# Arduino_EvalBoard.net
KiCad netlist of a schematic drawn in Altium Designer
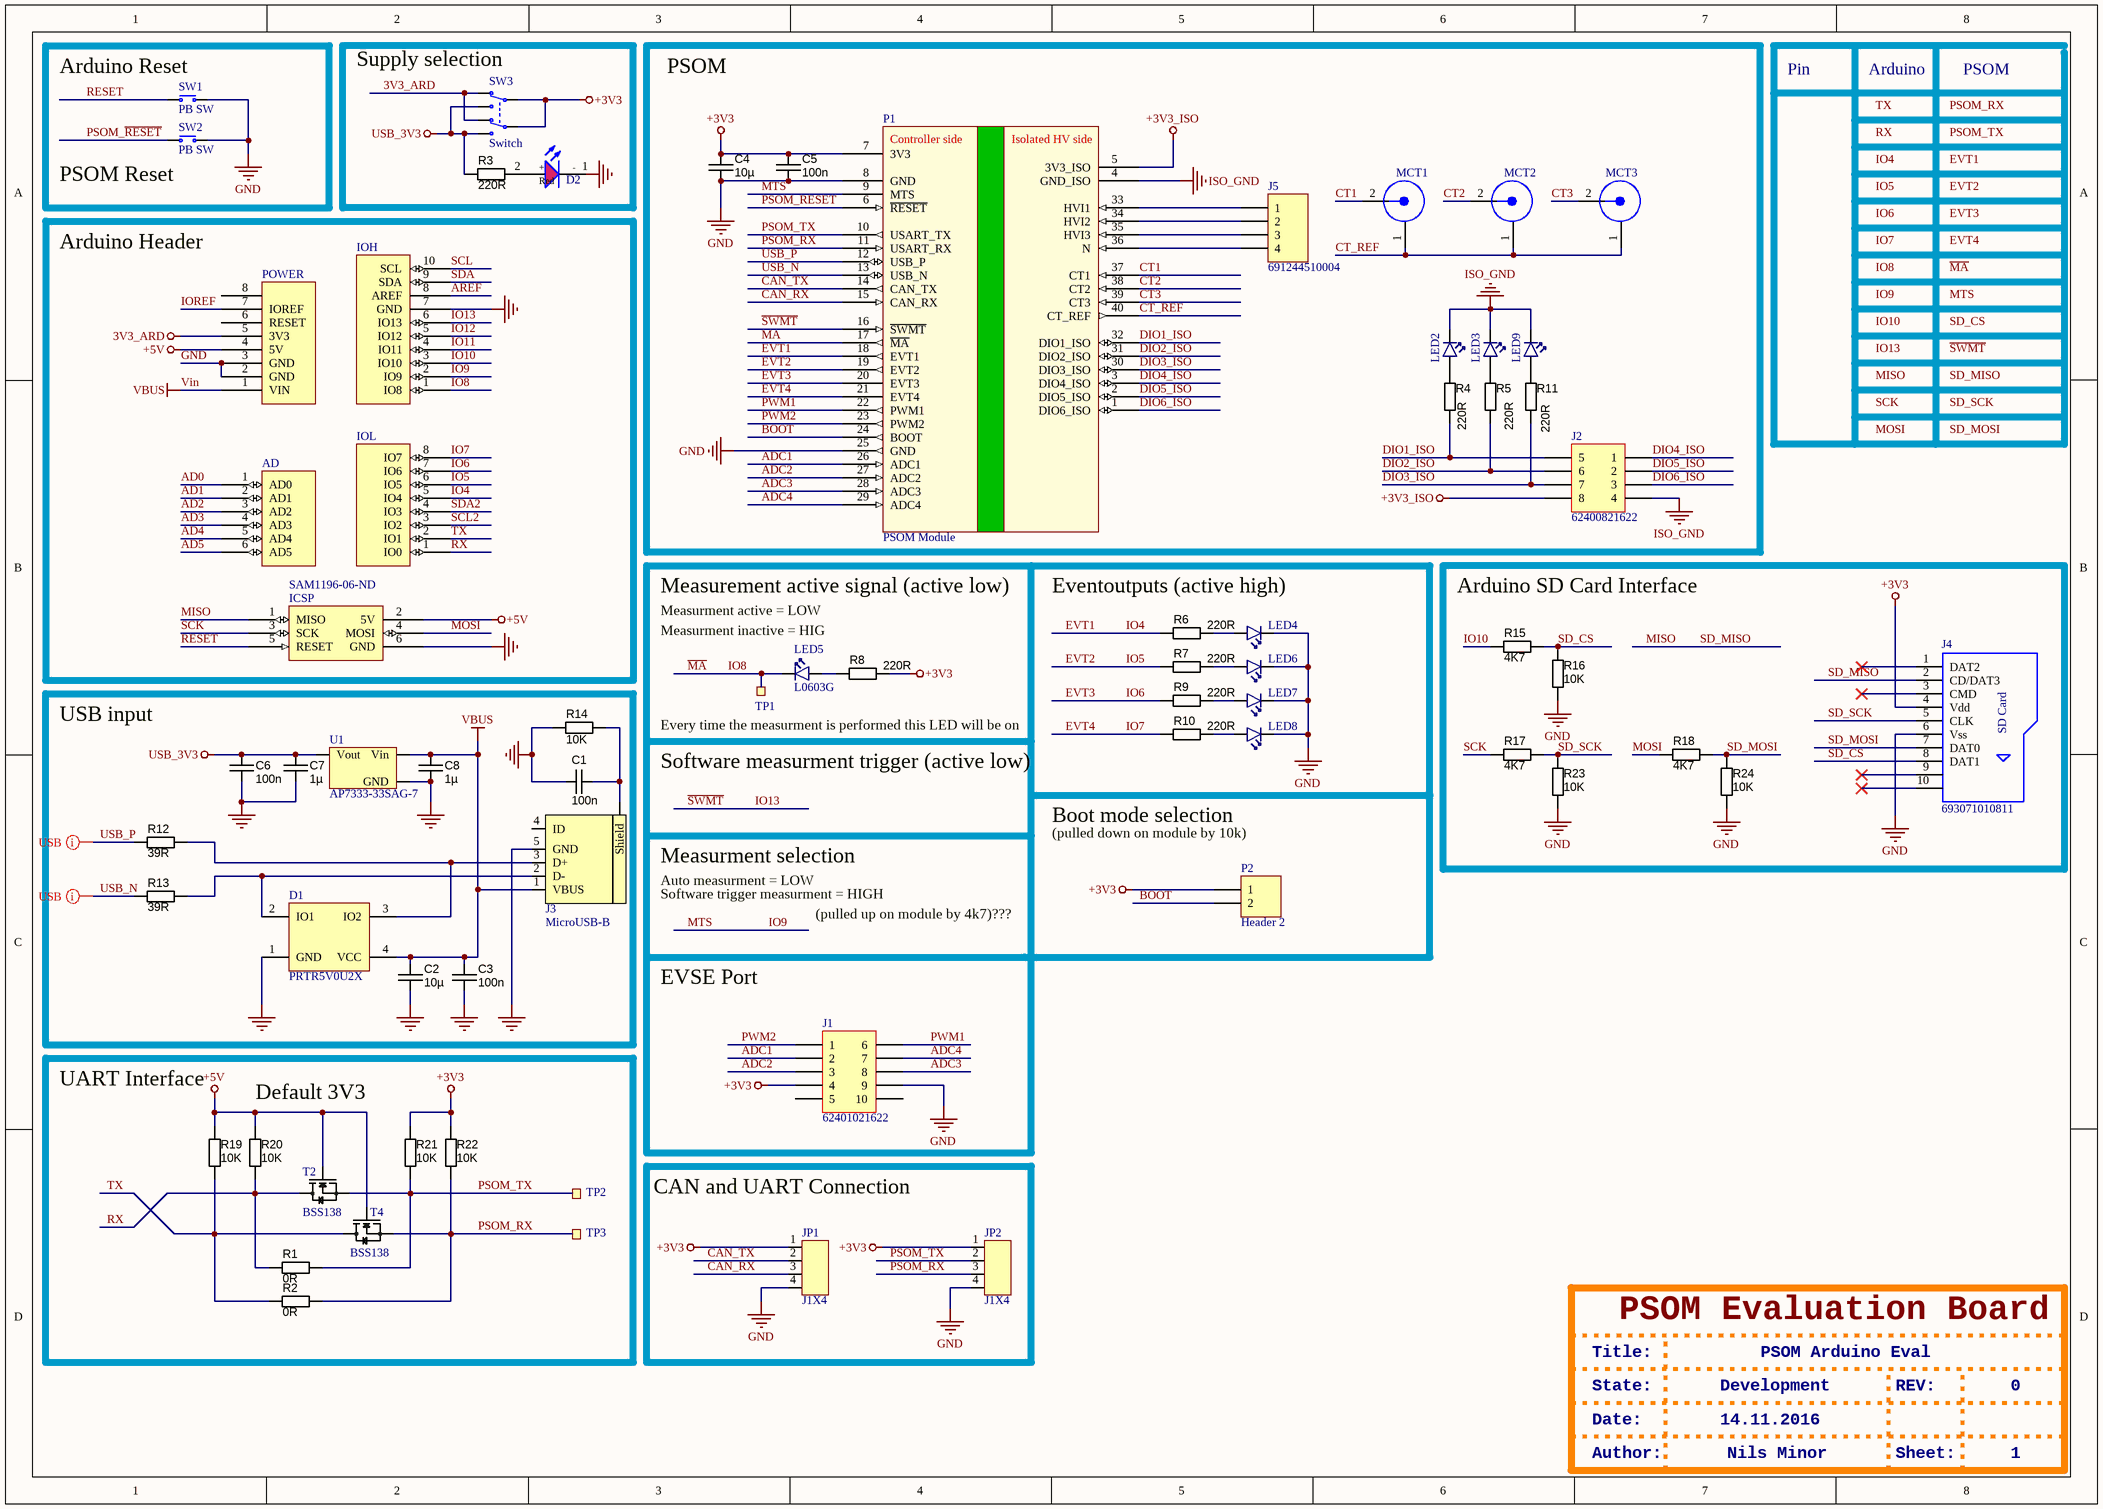
[diagram p0: Arduino EvalBoard.SchDoc]

(export (version "E")
  (design (tool "Eeschema 10.0.6"))
  (components
    (comp (ref "AD")
      (value "AD")
      (footprint "Header:Header 6x1 8.5mm")
      (libsource (lib "Header") (part "AD"))
    )
    (comp (ref "C1")
      (value "100n")
      (footprint "CAPC1608X90N")
      (description "Capacitor SMD Cer 100nF 10% 50V X7R 0603")
      (fields (field (name "TOLERANCE") "±10%") (field (name "Comment") "approved sub OK"))
      (libsource (lib "PBL - Capacitors") (part "CAPC_100n_0603_X7R_50V_10%"))
    )
    (comp (ref "C2")
      (value "10µ")
      (footprint "CAPC2012X135N")
      (description "Capacitor SMD Cer 10uF 10% 10V X5R 0805")
      (fields (field (name "TOLERANCE") "±10%") (field (name "Comment") "approved sub OK"))
      (libsource (lib "PBL - Capacitors") (part "CAPC_10u_0805_10V"))
    )
    (comp (ref "C3")
      (value "100n")
      (footprint "CAPC1608X90N")
      (description "Capacitor SMD Cer 100nF 10% 50V X7R 0603")
      (fields (field (name "TOLERANCE") "±10%") (field (name "Comment") "approved sub OK"))
      (libsource (lib "PBL - Capacitors") (part "CAPC_100n_0603_X7R_50V_10%"))
    )
    (comp (ref "C4")
      (value "10µ")
      (footprint "CAPC2012X135N")
      (description "Capacitor SMD Cer 10uF 10% 10V X5R 0805")
      (fields (field (name "TOLERANCE") "±10%") (field (name "Comment") "approved sub OK"))
      (libsource (lib "PBL - Capacitors") (part "CAPC_10u_0805_10V"))
    )
    (comp (ref "C5")
      (value "100n")
      (footprint "CAPC1608X90N")
      (description "Capacitor SMD Cer 100nF 10% 50V X7R 0603")
      (fields (field (name "TOLERANCE") "±10%") (field (name "Comment") "approved sub OK"))
      (libsource (lib "PBL - Capacitors") (part "CAPC_100n_0603_X7R_50V_10%"))
    )
    (comp (ref "C6")
      (value "100n")
      (footprint "CAPC1608X90N")
      (description "Capacitor SMD Cer 100nF 10% 50V X7R 0603")
      (fields (field (name "TOLERANCE") "±10%") (field (name "Comment") "approved sub OK"))
      (libsource (lib "PBL - Capacitors") (part "CAPC_100n_0603_X7R_50V_10%"))
    )
    (comp (ref "C7")
      (value "1µ")
      (footprint "CAPC1608X90N")
      (description "Capacitor SMD Cer 1uF 10% 16V X7R 0603")
      (fields (field (name "TOLERANCE") "±10%") (field (name "Comment") "approved sub OK"))
      (libsource (lib "PBL - Capacitors") (part "CAPC_1u_0603_X7R_16V_10%"))
    )
    (comp (ref "C8")
      (value "1µ")
      (footprint "CAPC1608X90N")
      (description "Capacitor SMD Cer 1uF 10% 16V X7R 0603")
      (fields (field (name "TOLERANCE") "±10%") (field (name "Comment") "approved sub OK"))
      (libsource (lib "PBL - Capacitors") (part "CAPC_1u_0603_X7R_16V_10%"))
    )
    (comp (ref "D1")
      (value "PRTR5V0U2X")
      (footprint "SOT190P230X110-4L")
      (description "Ultra low capacitance double rail-to-rail ESD protection diode")
      (fields
        (field (name "MANUFACTURER") "NXP")
        (field (name "2ND SOURCE PART NUMBER") "152-4157")
        (field (name "PUBLISHER") "Nordic Semiconductor")
      )
      (libsource (lib "Nordic Discrete DB") (part "PRTR5V0U2X"))
    )
    (comp (ref "D2")
      (value "150060RS75000")
      (footprint "WL-SMCW_0603")
      (description "WL-SMCW SMD chip LED top view mono-color waterclear, 0603, Red")
      (fields (field (name "MANUFACTURER") "Wurth Elektronik") (field (name "CREATED BY") "Baojun Chen"))
      (libsource (lib "WUERTH_SMD_LED") (part "WL-SMCW 0603, 150060RS75000"))
    )
    (comp (ref "ICSP")
      (value "ICSP")
      (footprint "ICSP")
      (fields (field (name "SUPPLIER PART NUMBER 5") "SAM1196-06-ND"))
      (libsource (lib "Header") (part "ICSP"))
    )
    (comp (ref "IOH")
      (value "IOH")
      (footprint "Header:Header 10x1 8.5mm")
      (libsource (lib "Header") (part "IOH"))
    )
    (comp (ref "IOL") (value "IOL") (footprint "Header 8x1 8.5mm") (libsource (lib "Header") (part "IOL")))
    (comp (ref "J1")
      (value "62401021622")
      (footprint "62401021622")
      (description "WR-WTB 2.00mm Male Dual Row Vertical Shrouded Header w. positive locking, 10 pins")
      (fields (field (name "MANUFACTURER") "Wurth Elektronik") (field (name "CREATED BY") "Baojun Chen"))
      (libsource (lib "ALTIUM-WTB_2_00_MALE_HORIZONTAL_SHROUDED_HEADER_6200XX11722-rev16b") (part "62401021622"))
    )
    (comp (ref "J2")
      (value "62400821622")
      (footprint "62400821622")
      (description "WR-WTB 2.00mm Male Dual Row Vertical Shrouded Header w. positive locking, 8 pins")
      (fields (field (name "MANUFACTURER") "Wurth Elektronik") (field (name "CREATED BY") "Baojun Chen"))
      (libsource (lib "ALTIUM-WTB_2_00_MALE_HORIZONTAL_SHROUDED_HEADER_6200XX11722-rev16b") (part "62400821622"))
    )
    (comp (ref "J3")
      (value "MicroUSB-B")
      (footprint "FCI_10118193-0001LF")
      (description "MicroUSB-B-SMT")
      (fields
        (field (name "PART NUMBER") "FCI 10118193-0001LF")
        (field (name "MANUFACTURER") "FCI")
        (field (name "PUBLISHER") "Nordic Semiconductor")
      )
      (libsource (lib "pca10040") (part "MiniUSB-AB-SMT"))
    )
    (comp (ref "J4")
      (value "693071010811")
      (footprint "693071010811")
      (description "WR-CRD Micro SD Card Connector Push & Push - 8 pins")
      (fields (field (name "PUBLISHER") "Wurth Elektronik"))
      (libsource (lib "WUERTH_SD_CARD") (part "693071010811"))
    )
    (comp (ref "J5")
      (value "691244510004")
      (footprint "691244510004")
      (description "WR-TBL Serie 2445 - 5.08mm Horizontal Entry Modular w. Rising Cage Clamp, 04p")
      (fields (field (name "PUBLISHER") "Wurth Elektronik"))
      (libsource (lib "ALTIUM-TBL_5_08_2445_HORIZONTAL_CABLE_ENTRY_W_RISING_CAGE_6912445100xx-rev1") (part "691244510004"))
    )
    (comp (ref "JP1")
      (value "J1X4")
      (footprint "SIP4")
      (description "Jumper 1x4, Stift, gerade, RM 2.54")
      (libsource (lib "WELNER") (part "J1X4"))
    )
    (comp (ref "JP2")
      (value "J1X4")
      (footprint "SIP4")
      (description "Jumper 1x4, Stift, gerade, RM 2.54")
      (libsource (lib "WELNER") (part "J1X4"))
    )
    (comp (ref "LED2")
      (value "L0603G")
      (footprint "LED_0603_G")
      (description "LED 0603, EL19-21SYGC")
      (fields
        (field (name "PART NUMBER") "EL19-21SYGC")
        (field (name "MANUFACTURER") "Everlight")
        (field (name "PUBLISHER") "Nordic Semiconductor")
      )
      (libsource (lib "pca10040") (part "D{colon}LED"))
    )
    (comp (ref "LED3")
      (value "L0603G")
      (footprint "LED_0603_G")
      (description "LED 0603, EL19-21SYGC")
      (fields
        (field (name "PART NUMBER") "EL19-21SYGC")
        (field (name "MANUFACTURER") "Everlight")
        (field (name "PUBLISHER") "Nordic Semiconductor")
      )
      (libsource (lib "pca10040") (part "D{colon}LED"))
    )
    (comp (ref "LED4")
      (value "L0603G")
      (footprint "LED_0603_G")
      (description "LED 0603, EL19-21SYGC")
      (fields
        (field (name "PART NUMBER") "EL19-21SYGC")
        (field (name "MANUFACTURER") "Everlight")
        (field (name "PUBLISHER") "Nordic Semiconductor")
      )
      (libsource (lib "pca10040") (part "D{colon}LED"))
    )
    (comp (ref "LED5")
      (value "L0603G")
      (footprint "LED_0603_G")
      (description "LED 0603, EL19-21SYGC")
      (fields
        (field (name "PART NUMBER") "EL19-21SYGC")
        (field (name "MANUFACTURER") "Everlight")
        (field (name "PUBLISHER") "Nordic Semiconductor")
      )
      (libsource (lib "pca10040") (part "D{colon}LED"))
    )
    (comp (ref "LED6")
      (value "L0603G")
      (footprint "LED_0603_G")
      (description "LED 0603, EL19-21SYGC")
      (fields
        (field (name "PART NUMBER") "EL19-21SYGC")
        (field (name "MANUFACTURER") "Everlight")
        (field (name "PUBLISHER") "Nordic Semiconductor")
      )
      (libsource (lib "pca10040") (part "D{colon}LED"))
    )
    (comp (ref "LED7")
      (value "L0603G")
      (footprint "LED_0603_G")
      (description "LED 0603, EL19-21SYGC")
      (fields
        (field (name "PART NUMBER") "EL19-21SYGC")
        (field (name "MANUFACTURER") "Everlight")
        (field (name "PUBLISHER") "Nordic Semiconductor")
      )
      (libsource (lib "pca10040") (part "D{colon}LED"))
    )
    (comp (ref "LED8")
      (value "L0603G")
      (footprint "LED_0603_G")
      (description "LED 0603, EL19-21SYGC")
      (fields
        (field (name "PART NUMBER") "EL19-21SYGC")
        (field (name "MANUFACTURER") "Everlight")
        (field (name "PUBLISHER") "Nordic Semiconductor")
      )
      (libsource (lib "pca10040") (part "D{colon}LED"))
    )
    (comp (ref "LED9")
      (value "L0603G")
      (footprint "LED_0603_G")
      (description "LED 0603, EL19-21SYGC")
      (fields
        (field (name "PART NUMBER") "EL19-21SYGC")
        (field (name "MANUFACTURER") "Everlight")
        (field (name "PUBLISHER") "Nordic Semiconductor")
      )
      (libsource (lib "pca10040") (part "D{colon}LED"))
    )
    (comp (ref "MCT1")
      (value "~")
      (footprint "BNC_Female")
      (description "BNC Conector")
      (libsource (lib "minor") (part "BNC_Buchse"))
    )
    (comp (ref "MCT2")
      (value "~")
      (footprint "BNC_Female")
      (description "BNC Conector")
      (libsource (lib "minor") (part "BNC_Buchse"))
    )
    (comp (ref "MCT3")
      (value "~")
      (footprint "BNC_Female")
      (description "BNC Conector")
      (libsource (lib "minor") (part "BNC_Buchse"))
    )
    (comp (ref "P1")
      (value "PSOM Module")
      (footprint "PSOM_SMD")
      (description "Power analysis system on a module")
      (fields (field (name "CONTACT") "nilsminor@web.de") (field (name "CREATOR") "Nils Minor"))
      (libsource (lib "PSOM") (part "PSOM_Module_1"))
    )
    (comp (ref "P2")
      (value "Header 2")
      (footprint "HDR1X2")
      (description "Header, 2-Pin")
      (fields (field (name "PUBLISHER") "Altium Limited"))
      (libsource (lib "Miscellaneous Connectors") (part "Header 2"))
    )
    (comp (ref "POWER")
      (value "POWER_UNO")
      (footprint "Header 8x1 8.5mm")
      (libsource (lib "Header") (part "POWER_UNO"))
    )
    (comp (ref "R1")
      (value "0R")
      (footprint "RESC1608N_ZERO")
      (description "Resistor SMD chip 0.0 Ohm 0.1W 0603")
      (fields (field (name "TOLERANCE") "±5%") (field (name "Comment") "Thick Film"))
      (libsource (lib "PBL - Resistors") (part "RES_0R_0603"))
    )
    (comp (ref "R2")
      (value "0R")
      (footprint "RESC1608N_ZERO")
      (description "Resistor SMD chip 0.0 Ohm 0.1W 0603")
      (fields (field (name "TOLERANCE") "±5%") (field (name "Comment") "Thick Film"))
      (libsource (lib "PBL - Resistors") (part "RES_0R_0603"))
    )
    (comp (ref "R3")
      (value "220R")
      (footprint "RESC1608X55N")
      (description "Resistor SMD chip 220 Ohm 0.1W 5% 0603")
      (fields (field (name "TOLERANCE") "±5%") (field (name "Comment") "Thick Film"))
      (libsource (lib "") (part "RES_220R_0603_5%_1"))
    )
    (comp (ref "R4")
      (value "220R")
      (footprint "RESC1005X40N")
      (description "Resistor SMD chip 220 Ohm 0.1W 5% 0603")
      (fields (field (name "TOLERANCE") "±5%") (field (name "Comment") "Thick Film"))
      (libsource (lib "PBL - Resistors") (part "RES_220R_0603_5%"))
    )
    (comp (ref "R5")
      (value "220R")
      (footprint "RESC1005X40N")
      (description "Resistor SMD chip 220 Ohm 0.1W 5% 0603")
      (fields (field (name "TOLERANCE") "±5%") (field (name "Comment") "Thick Film"))
      (libsource (lib "PBL - Resistors") (part "RES_220R_0603_5%"))
    )
    (comp (ref "R6")
      (value "220R")
      (footprint "RESC1005X40N")
      (description "Resistor SMD chip 220 Ohm 0.1W 5% 0603")
      (fields (field (name "TOLERANCE") "±5%") (field (name "Comment") "Thick Film"))
      (libsource (lib "") (part "RES_220R_0603_5%_1"))
    )
    (comp (ref "R7")
      (value "220R")
      (footprint "RESC1005X40N")
      (description "Resistor SMD chip 220 Ohm 0.1W 5% 0603")
      (fields (field (name "TOLERANCE") "±5%") (field (name "Comment") "Thick Film"))
      (libsource (lib "") (part "RES_220R_0603_5%_1"))
    )
    (comp (ref "R8")
      (value "220R")
      (footprint "RESC1005X40N")
      (description "Resistor SMD chip 220 Ohm 0.1W 5% 0603")
      (fields (field (name "TOLERANCE") "±5%") (field (name "Comment") "Thick Film"))
      (libsource (lib "") (part "RES_220R_0603_5%_1"))
    )
    (comp (ref "R9")
      (value "220R")
      (footprint "RESC1005X40N")
      (description "Resistor SMD chip 220 Ohm 0.1W 5% 0603")
      (fields (field (name "TOLERANCE") "±5%") (field (name "Comment") "Thick Film"))
      (libsource (lib "") (part "RES_220R_0603_5%_1"))
    )
    (comp (ref "R10")
      (value "220R")
      (footprint "RESC1005X40N")
      (description "Resistor SMD chip 220 Ohm 0.1W 5% 0603")
      (fields (field (name "TOLERANCE") "±5%") (field (name "Comment") "Thick Film"))
      (libsource (lib "") (part "RES_220R_0603_5%_1"))
    )
    (comp (ref "R11")
      (value "220R")
      (footprint "RESC1005X40N")
      (description "Resistor SMD chip 220 Ohm 0.1W 5% 0603")
      (fields (field (name "TOLERANCE") "±5%") (field (name "Comment") "Thick Film"))
      (libsource (lib "PBL - Resistors") (part "RES_220R_0603_5%"))
    )
    (comp (ref "R12")
      (value "39R")
      (footprint "RESC1608X55N")
      (description "Resistor SMD chip 39 Ohm 0.1W 5% 0603")
      (fields (field (name "TOLERANCE") "±5%") (field (name "Comment") "Thick Film"))
      (libsource (lib "PBL - Resistors") (part "RES_39R_0603_5%"))
    )
    (comp (ref "R13")
      (value "39R")
      (footprint "RESC1608X55N")
      (description "Resistor SMD chip 39 Ohm 0.1W 5% 0603")
      (fields (field (name "TOLERANCE") "±5%") (field (name "Comment") "Thick Film"))
      (libsource (lib "PBL - Resistors") (part "RES_39R_0603_5%"))
    )
    (comp (ref "R14")
      (value "10K")
      (footprint "RESC1005X40N")
      (description "Resistor SMD chip 10k Ohm 0.063W 5% 0402")
      (fields (field (name "TOLERANCE") "±5%") (field (name "Comment") "Thick Film"))
      (libsource (lib "PBL - Resistors") (part "RES_10K_0402_5%"))
    )
    (comp (ref "R15")
      (value "4K7")
      (footprint "RESC1005X40N")
      (description "Resistor SMD chip 4.7K Ohm 0.1W 1% 0603")
      (fields
        (field (name "MANUFACTURER") "Yageo")
        (field (name "MANUFACTURER PART NUMBER") "RC0603FR-074K7L")
      )
      (libsource (lib "PBL - Resistors") (part "RES_4K7_0603_1%"))
    )
    (comp (ref "R16")
      (value "10K")
      (footprint "RESC1005X40N")
      (description "Resistor SMD chip 10k Ohm 0.063W 5% 0402")
      (fields (field (name "TOLERANCE") "±5%") (field (name "Comment") "Thick Film"))
      (libsource (lib "") (part "RES_10K_0402_5%_1"))
    )
    (comp (ref "R17")
      (value "4K7")
      (footprint "RESC1005X40N")
      (description "Resistor SMD chip 4.7K Ohm 0.1W 1% 0603")
      (fields
        (field (name "MANUFACTURER") "Yageo")
        (field (name "MANUFACTURER PART NUMBER") "RC0603FR-074K7L")
      )
      (libsource (lib "PBL - Resistors") (part "RES_4K7_0603_1%"))
    )
    (comp (ref "R18")
      (value "4K7")
      (footprint "RESC1005X40N")
      (description "Resistor SMD chip 4.7K Ohm 0.1W 1% 0603")
      (fields
        (field (name "MANUFACTURER") "Yageo")
        (field (name "MANUFACTURER PART NUMBER") "RC0603FR-074K7L")
      )
      (libsource (lib "PBL - Resistors") (part "RES_4K7_0603_1%"))
    )
    (comp (ref "R19")
      (value "10K")
      (footprint "RESC1005X40N")
      (description "Resistor SMD chip 10k Ohm 0.063W 5% 0402")
      (fields (field (name "TOLERANCE") "±5%") (field (name "Comment") "Thick Film"))
      (libsource (lib "PBL - Resistors") (part "RES_10K_0402_5%"))
    )
    (comp (ref "R20")
      (value "10K")
      (footprint "RESC1005X40N")
      (description "Resistor SMD chip 10k Ohm 0.063W 5% 0402")
      (fields (field (name "TOLERANCE") "±5%") (field (name "Comment") "Thick Film"))
      (libsource (lib "PBL - Resistors") (part "RES_10K_0402_5%"))
    )
    (comp (ref "R21")
      (value "10K")
      (footprint "RESC1005X40N")
      (description "Resistor SMD chip 10k Ohm 0.063W 5% 0402")
      (fields (field (name "TOLERANCE") "±5%") (field (name "Comment") "Thick Film"))
      (libsource (lib "PBL - Resistors") (part "RES_10K_0402_5%"))
    )
    (comp (ref "R22")
      (value "10K")
      (footprint "RESC1005X40N")
      (description "Resistor SMD chip 10k Ohm 0.063W 5% 0402")
      (fields (field (name "TOLERANCE") "±5%") (field (name "Comment") "Thick Film"))
      (libsource (lib "PBL - Resistors") (part "RES_10K_0402_5%"))
    )
    (comp (ref "R23")
      (value "10K")
      (footprint "RESC1005X40N")
      (description "Resistor SMD chip 10k Ohm 0.063W 5% 0402")
      (fields (field (name "TOLERANCE") "±5%") (field (name "Comment") "Thick Film"))
      (libsource (lib "") (part "RES_10K_0402_5%_1"))
    )
    (comp (ref "R24")
      (value "10K")
      (footprint "RESC1005X40N")
      (description "Resistor SMD chip 10k Ohm 0.063W 5% 0402")
      (fields (field (name "TOLERANCE") "±5%") (field (name "Comment") "Thick Film"))
      (libsource (lib "") (part "RES_10K_0402_5%_1"))
    )
    (comp (ref "SW1")
      (value "PB SW")
      (footprint "ALPS_SKHUxxx010_WO_GND")
      (description "ALPS - SKHUALE010 - Tactile Switch, SPNO, SMD, 6.5x6.2x2.5mm")
      (fields
        (field (name "PART NUMBER") "ALPS_SKHUALE010")
        (field (name "MANUFACTURER") "Alps")
        (field (name "PUBLISHER") "Nordic Semiconductor")
      )
      (libsource (lib "pca10040") (part "SW-PB"))
    )
    (comp (ref "SW2")
      (value "PB SW")
      (footprint "ALPS_SKHUxxx010_WO_GND")
      (description "ALPS - SKHUALE010 - Tactile Switch, SPNO, SMD, 6.5x6.2x2.5mm")
      (fields
        (field (name "PART NUMBER") "ALPS_SKHUALE010")
        (field (name "MANUFACTURER") "Alps")
        (field (name "PUBLISHER") "Nordic Semiconductor")
      )
      (libsource (lib "pca10040") (part "SW-PB"))
    )
    (comp (ref "SW3")
      (value "Switch")
      (footprint "JS202011SCQN")
      (description "SMD slide Switch (ON-ON)")
      (fields
        (field (name "PART NUMBER") "JS202011SCQN")
        (field (name "MANUFACTURER") "C&K Components")
        (field (name "PUBLISHER") "Nordic Semiconductor")
      )
      (libsource (lib "pca10040") (part "SW-DPDT"))
    )
    (comp (ref "T2")
      (value "BSS138")
      (footprint "SOT23-3")
      (description "N-Chanel FET,SMD")
      (libsource (lib "BOMEDUS") (part "BSS138"))
    )
    (comp (ref "T4")
      (value "BSS138")
      (footprint "SOT23-3")
      (description "N-Chanel FET,SMD")
      (libsource (lib "BOMEDUS") (part "BSS138"))
    )
    (comp (ref "TP1")
      (value "Ø1.0mm,SMD")
      (footprint "TP_SMD_Ø1.0mm")
      (description "1.0mm circular SMD testpad")
      (fields
        (field (name "PART NUMBER") "TP_SMD_Ø1.0MM")
        (field (name "MANUFACTURER") "Nordic Semiconductor")
        (field (name "PUBLISHER") "Nordic Semiconductor")
      )
      (libsource (lib "pca10040") (part "TESTPAD"))
    )
    (comp (ref "TP2")
      (value "Ø1.0mm,SMD")
      (footprint "TP_SMD_Ø1.0mm")
      (description "1.0mm circular SMD testpad")
      (fields
        (field (name "PART NUMBER") "TP_SMD_Ø1.0MM")
        (field (name "MANUFACTURER") "Nordic Semiconductor")
        (field (name "PUBLISHER") "Nordic Semiconductor")
      )
      (libsource (lib "") (part "TESTPAD_1"))
    )
    (comp (ref "TP3")
      (value "Ø1.0mm,SMD")
      (footprint "TP_SMD_Ø1.0mm")
      (description "1.0mm circular SMD testpad")
      (fields
        (field (name "PART NUMBER") "TP_SMD_Ø1.0MM")
        (field (name "MANUFACTURER") "Nordic Semiconductor")
        (field (name "PUBLISHER") "Nordic Semiconductor")
      )
      (libsource (lib "") (part "TESTPAD_1"))
    )
    (comp (ref "U1")
      (value "AP7333-33SAG-7")
      (footprint "SOT-23A")
      (description "300mA, Low Quiescent Current, Fast Transient Low Dropout Linear Regulator")
      (fields (field (name "MANUFACTURER") "Diodes Incorporated"))
      (libsource (lib "pca10040") (part "AP7333-XXSAG"))
    )
  )
  (nets
    (net (code "1") (name "+3V3") (class "Default")
      (node (ref "C4") (pin "1") (pintype "passive"))
      (node (ref "C5") (pin "1") (pintype "passive"))
      (node (ref "J1") (pin "4") (pinfunction "4_4") (pintype "passive"))
      (node (ref "J4") (pin "4") (pinfunction "Vdd_4") (pintype "passive"))
      (node (ref "JP1") (pin "1") (pintype "passive"))
      (node (ref "JP2") (pin "1") (pintype "passive"))
      (node (ref "P1") (pin "7") (pinfunction "3V3_7") (pintype "power_in"))
      (node (ref "P2") (pin "1") (pinfunction "1_1") (pintype "passive"))
      (node (ref "R21") (pin "2") (pinfunction "2_2") (pintype "passive"))
      (node (ref "R22") (pin "2") (pinfunction "2_2") (pintype "passive"))
      (node (ref "R8") (pin "1") (pinfunction "1_1") (pintype "passive"))
      (node (ref "SW3") (pin "2") (pinfunction "COM-1_2") (pintype "passive"))
      (node (ref "SW3") (pin "5") (pinfunction "COM-2_5") (pintype "passive"))
    )
    (net (code "2") (name "+3V3_ISO") (class "Default")
      (node (ref "J2") (pin "8") (pinfunction "8_8") (pintype "passive"))
      (node (ref "P1") (pin "5") (pinfunction "3V3_ISO_5") (pintype "power_in"))
    )
    (net (code "3") (name "+5V") (class "Default")
      (node (ref "ICSP") (pin "2") (pinfunction "5V_2") (pintype "power_in"))
      (node (ref "POWER") (pin "4") (pinfunction "5V_4") (pintype "power_in"))
      (node (ref "R19") (pin "2") (pinfunction "2_2") (pintype "passive"))
      (node (ref "R20") (pin "2") (pinfunction "2_2") (pintype "passive"))
      (node (ref "T2") (pin "1") (pinfunction "G_1") (pintype "passive"))
      (node (ref "T4") (pin "1") (pinfunction "G_1") (pintype "passive"))
    )
    (net (code "5") (name "/AD0") (class "Default")
      (node (ref "AD") (pin "1") (pinfunction "AD0_1") (pintype "bidirectional"))
    )
    (net (code "6") (name "/AD1") (class "Default")
      (node (ref "AD") (pin "2") (pinfunction "AD1_2") (pintype "bidirectional"))
    )
    (net (code "7") (name "/AD2") (class "Default")
      (node (ref "AD") (pin "3") (pinfunction "AD2_3") (pintype "bidirectional"))
    )
    (net (code "8") (name "/AD3") (class "Default")
      (node (ref "AD") (pin "4") (pinfunction "AD3_4") (pintype "bidirectional"))
    )
    (net (code "9") (name "/AD4") (class "Default")
      (node (ref "AD") (pin "5") (pinfunction "AD4_5") (pintype "bidirectional"))
    )
    (net (code "10") (name "/AD5") (class "Default")
      (node (ref "AD") (pin "6") (pinfunction "AD5_6") (pintype "bidirectional"))
    )
    (net (code "11") (name "/ADC1") (class "Default")
      (node (ref "J1") (pin "2") (pinfunction "2_2") (pintype "passive"))
      (node (ref "P1") (pin "26") (pinfunction "ADC1_26") (pintype "input"))
    )
    (net (code "12") (name "/ADC2") (class "Default")
      (node (ref "J1") (pin "3") (pinfunction "3_3") (pintype "passive"))
      (node (ref "P1") (pin "27") (pinfunction "ADC2_27") (pintype "input"))
    )
    (net (code "13") (name "/ADC3") (class "Default")
      (node (ref "J1") (pin "8") (pinfunction "8_8") (pintype "passive"))
      (node (ref "P1") (pin "28") (pinfunction "ADC3_28") (pintype "input"))
    )
    (net (code "14") (name "/ADC4") (class "Default")
      (node (ref "J1") (pin "7") (pinfunction "7_7") (pintype "passive"))
      (node (ref "P1") (pin "29") (pinfunction "ADC4_29") (pintype "input"))
    )
    (net (code "15") (name "/AREF") (class "Default")
      (node (ref "IOH") (pin "8") (pinfunction "AREF_8") (pintype "passive"))
    )
    (net (code "16") (name "/BOOT") (class "Default")
      (node (ref "P1") (pin "24") (pinfunction "BOOT_24") (pintype "output"))
      (node (ref "P2") (pin "2") (pinfunction "2_2") (pintype "passive"))
    )
    (net (code "17") (name "/CAN_RX") (class "Default")
      (node (ref "JP1") (pin "3") (pintype "passive"))
      (node (ref "P1") (pin "15") (pinfunction "CAN_RX_15") (pintype "input"))
    )
    (net (code "18") (name "/CAN_TX") (class "Default")
      (node (ref "JP1") (pin "2") (pintype "passive"))
      (node (ref "P1") (pin "14") (pinfunction "CAN_TX_14") (pintype "output"))
    )
    (net (code "19") (name "/CT1") (class "Default")
      (node (ref "MCT1") (pin "2") (pinfunction "2_2") (pintype "passive"))
      (node (ref "P1") (pin "37") (pinfunction "CT1_37") (pintype "input"))
    )
    (net (code "20") (name "/CT2") (class "Default")
      (node (ref "MCT2") (pin "2") (pinfunction "2_2") (pintype "passive"))
      (node (ref "P1") (pin "38") (pinfunction "CT2_38") (pintype "input"))
    )
    (net (code "21") (name "/CT3") (class "Default")
      (node (ref "MCT3") (pin "2") (pinfunction "2_2") (pintype "passive"))
      (node (ref "P1") (pin "39") (pinfunction "CT3_39") (pintype "input"))
    )
    (net (code "22") (name "/CT_REF") (class "Default")
      (node (ref "MCT1") (pin "1") (pinfunction "1_1") (pintype "passive"))
      (node (ref "MCT2") (pin "1") (pinfunction "1_1") (pintype "passive"))
      (node (ref "MCT3") (pin "1") (pinfunction "1_1") (pintype "passive"))
      (node (ref "P1") (pin "40") (pinfunction "CT_REF_40") (pintype "output"))
    )
    (net (code "23") (name "/DIO1_ISO") (class "Default")
      (node (ref "J2") (pin "5") (pinfunction "5_5") (pintype "passive"))
      (node (ref "P1") (pin "32") (pinfunction "DIO1_ISO_32") (pintype "bidirectional"))
      (node (ref "R4") (pin "2") (pinfunction "2_2") (pintype "passive"))
    )
    (net (code "24") (name "/DIO2_ISO") (class "Default")
      (node (ref "J2") (pin "6") (pinfunction "6_6") (pintype "passive"))
      (node (ref "P1") (pin "31") (pinfunction "DIO2_ISO_31") (pintype "bidirectional"))
      (node (ref "R5") (pin "2") (pinfunction "2_2") (pintype "passive"))
    )
    (net (code "25") (name "/DIO3_ISO") (class "Default")
      (node (ref "J2") (pin "7") (pinfunction "7_7") (pintype "passive"))
      (node (ref "P1") (pin "30") (pinfunction "DIO3_ISO_30") (pintype "bidirectional"))
      (node (ref "R11") (pin "2") (pinfunction "2_2") (pintype "passive"))
    )
    (net (code "26") (name "/DIO4_ISO") (class "Default")
      (node (ref "J2") (pin "1") (pinfunction "1_1") (pintype "passive"))
      (node (ref "P1") (pin "3") (pinfunction "DIO4_ISO_3") (pintype "bidirectional"))
    )
    (net (code "27") (name "/DIO5_ISO") (class "Default")
      (node (ref "J2") (pin "2") (pinfunction "2_2") (pintype "passive"))
      (node (ref "P1") (pin "2") (pinfunction "DIO5_ISO_2") (pintype "bidirectional"))
    )
    (net (code "28") (name "/DIO6_ISO") (class "Default")
      (node (ref "J2") (pin "3") (pinfunction "3_3") (pintype "passive"))
      (node (ref "P1") (pin "1") (pinfunction "DIO6_ISO_1") (pintype "bidirectional"))
    )
    (net (code "29") (name "/EVT1") (class "Default")
      (node (ref "IOL") (pin "5") (pinfunction "IO4_5") (pintype "bidirectional"))
      (node (ref "P1") (pin "18") (pinfunction "EVT1_18") (pintype "output"))
      (node (ref "R6") (pin "2") (pinfunction "2_2") (pintype "passive"))
    )
    (net (code "30") (name "/EVT2") (class "Default")
      (node (ref "IOL") (pin "6") (pinfunction "IO5_6") (pintype "bidirectional"))
      (node (ref "P1") (pin "19") (pinfunction "EVT2_19") (pintype "output"))
      (node (ref "R7") (pin "2") (pinfunction "2_2") (pintype "passive"))
    )
    (net (code "31") (name "/EVT3") (class "Default")
      (node (ref "IOL") (pin "7") (pinfunction "IO6_7") (pintype "bidirectional"))
      (node (ref "P1") (pin "20") (pinfunction "EVT3_20") (pintype "passive"))
      (node (ref "R9") (pin "2") (pinfunction "2_2") (pintype "passive"))
    )
    (net (code "32") (name "/EVT4") (class "Default")
      (node (ref "IOL") (pin "8") (pinfunction "IO7_8") (pintype "bidirectional"))
      (node (ref "P1") (pin "21") (pinfunction "EVT4_21") (pintype "passive"))
      (node (ref "R10") (pin "2") (pinfunction "2_2") (pintype "passive"))
    )
    (net (code "33") (name "/IO8") (class "Default")
      (node (ref "IOH") (pin "1") (pinfunction "IO8_1") (pintype "bidirectional"))
      (node (ref "LED5") (pin "1") (pinfunction "C_1") (pintype "passive"))
      (node (ref "P1") (pin "17") (pinfunction "~{MA}_17") (pintype "output"))
      (node (ref "TP1") (pin "1") (pinfunction "1_1") (pintype "passive"))
    )
    (net (code "34") (name "/IO9") (class "Default")
      (node (ref "IOH") (pin "2") (pinfunction "IO9_2") (pintype "bidirectional"))
      (node (ref "P1") (pin "9") (pinfunction "MTS_9") (pintype "passive"))
    )
    (net (code "35") (name "/IO10") (class "Default")
      (node (ref "IOH") (pin "3") (pinfunction "IO10_3") (pintype "bidirectional"))
      (node (ref "R15") (pin "2") (pinfunction "2_2") (pintype "passive"))
    )
    (net (code "36") (name "/IO11") (class "Default")
      (node (ref "IOH") (pin "4") (pinfunction "IO11_4") (pintype "bidirectional"))
    )
    (net (code "37") (name "/IO12") (class "Default")
      (node (ref "IOH") (pin "5") (pinfunction "IO12_5") (pintype "bidirectional"))
    )
    (net (code "38") (name "/IO13") (class "Default")
      (node (ref "IOH") (pin "6") (pinfunction "IO13_6") (pintype "bidirectional"))
      (node (ref "P1") (pin "16") (pinfunction "~{SWMT}_16") (pintype "input"))
    )
    (net (code "39") (name "/IOREF") (class "Default")
      (node (ref "POWER") (pin "7") (pinfunction "IOREF_7") (pintype "power_in"))
    )
    (net (code "40") (name "/MISO") (class "Default")
      (node (ref "ICSP") (pin "1") (pinfunction "MISO_1") (pintype "bidirectional"))
      (node (ref "J4") (pin "2") (pinfunction "CD/DAT3_2") (pintype "passive"))
    )
    (net (code "41") (name "/MOSI") (class "Default")
      (node (ref "ICSP") (pin "4") (pinfunction "MOSI_4") (pintype "bidirectional"))
      (node (ref "R18") (pin "2") (pinfunction "2_2") (pintype "passive"))
    )
    (net (code "42") (name "/PSOM_RX") (class "Default")
      (node (ref "JP2") (pin "3") (pintype "passive"))
      (node (ref "P1") (pin "11") (pinfunction "USART_RX_11") (pintype "input"))
      (node (ref "R2") (pin "2") (pinfunction "2_2") (pintype "passive"))
      (node (ref "R22") (pin "1") (pinfunction "1_1") (pintype "passive"))
      (node (ref "T4") (pin "2") (pinfunction "S_2") (pintype "passive"))
      (node (ref "TP3") (pin "1") (pinfunction "1_1") (pintype "passive"))
    )
    (net (code "43") (name "/PSOM_TX") (class "Default")
      (node (ref "JP2") (pin "2") (pintype "passive"))
      (node (ref "P1") (pin "10") (pinfunction "USART_TX_10") (pintype "output"))
      (node (ref "R1") (pin "2") (pinfunction "2_2") (pintype "passive"))
      (node (ref "R21") (pin "1") (pinfunction "1_1") (pintype "passive"))
      (node (ref "T2") (pin "2") (pinfunction "S_2") (pintype "passive"))
      (node (ref "TP2") (pin "1") (pinfunction "1_1") (pintype "passive"))
    )
    (net (code "44") (name "/PSOM_~{RESET}") (class "Default")
      (node (ref "P1") (pin "6") (pinfunction "~{RESET}_6") (pintype "input"))
      (node (ref "SW2") (pin "2") (pinfunction "COM_2") (pintype "passive"))
    )
    (net (code "45") (name "/PWM1") (class "Default")
      (node (ref "J1") (pin "6") (pinfunction "6_6") (pintype "passive"))
      (node (ref "P1") (pin "22") (pinfunction "PWM1_22") (pintype "output"))
    )
    (net (code "46") (name "/PWM2") (class "Default")
      (node (ref "J1") (pin "1") (pinfunction "1_1") (pintype "passive"))
      (node (ref "P1") (pin "23") (pinfunction "PWM2_23") (pintype "output"))
    )
    (net (code "47") (name "/RESET") (class "Default")
      (node (ref "ICSP") (pin "5") (pinfunction "RESET_5") (pintype "input"))
      (node (ref "SW1") (pin "2") (pinfunction "COM_2") (pintype "passive"))
    )
    (net (code "48") (name "/RX") (class "Default")
      (node (ref "IOL") (pin "1") (pinfunction "IO0_1") (pintype "bidirectional"))
      (node (ref "R1") (pin "1") (pinfunction "1_1") (pintype "passive"))
      (node (ref "R20") (pin "1") (pinfunction "1_1") (pintype "passive"))
      (node (ref "T2") (pin "3") (pinfunction "D_3") (pintype "passive"))
    )
    (net (code "49") (name "/SCK") (class "Default")
      (node (ref "ICSP") (pin "3") (pinfunction "SCK_3") (pintype "bidirectional"))
      (node (ref "R17") (pin "2") (pinfunction "2_2") (pintype "passive"))
    )
    (net (code "50") (name "/SCL") (class "Default")
      (node (ref "IOH") (pin "10") (pinfunction "SCL_10") (pintype "bidirectional"))
    )
    (net (code "51") (name "/SCL2") (class "Default")
      (node (ref "IOL") (pin "3") (pinfunction "IO2_3") (pintype "bidirectional"))
    )
    (net (code "52") (name "/SDA") (class "Default")
      (node (ref "IOH") (pin "9") (pinfunction "SDA_9") (pintype "bidirectional"))
    )
    (net (code "53") (name "/SDA2") (class "Default")
      (node (ref "IOL") (pin "4") (pinfunction "IO3_4") (pintype "bidirectional"))
    )
    (net (code "54") (name "/SD_CS") (class "Default")
      (node (ref "J4") (pin "8") (pinfunction "DAT1_8") (pintype "passive"))
      (node (ref "R15") (pin "1") (pinfunction "1_1") (pintype "passive"))
      (node (ref "R16") (pin "1") (pinfunction "1_1") (pintype "passive"))
    )
    (net (code "55") (name "/SD_MOSI") (class "Default")
      (node (ref "J4") (pin "7") (pinfunction "DAT0_7") (pintype "passive"))
      (node (ref "R18") (pin "1") (pinfunction "1_1") (pintype "passive"))
      (node (ref "R24") (pin "1") (pinfunction "1_1") (pintype "passive"))
    )
    (net (code "56") (name "/SD_SCK") (class "Default")
      (node (ref "J4") (pin "5") (pinfunction "CLK_5") (pintype "passive"))
      (node (ref "R17") (pin "1") (pinfunction "1_1") (pintype "passive"))
      (node (ref "R23") (pin "1") (pinfunction "1_1") (pintype "passive"))
    )
    (net (code "57") (name "/TX") (class "Default")
      (node (ref "IOL") (pin "2") (pinfunction "IO1_2") (pintype "bidirectional"))
      (node (ref "R19") (pin "1") (pinfunction "1_1") (pintype "passive"))
      (node (ref "R2") (pin "1") (pinfunction "1_1") (pintype "passive"))
      (node (ref "T4") (pin "3") (pinfunction "D_3") (pintype "passive"))
    )
    (net (code "58") (name "/USB_N") (class "Default")
      (node (ref "P1") (pin "13") (pinfunction "USB_N_13") (pintype "bidirectional"))
      (node (ref "R13") (pin "1") (pinfunction "1_1") (pintype "passive"))
    )
    (net (code "59") (name "/USB_P") (class "Default")
      (node (ref "P1") (pin "12") (pinfunction "USB_P_12") (pintype "bidirectional"))
      (node (ref "R12") (pin "1") (pinfunction "1_1") (pintype "passive"))
    )
    (net (code "60") (name "3V3_ARD") (class "Default")
      (node (ref "POWER") (pin "5") (pinfunction "3V3_5") (pintype "power_in"))
      (node (ref "SW3") (pin "3") (pinfunction "N.C-1_3") (pintype "passive"))
      (node (ref "SW3") (pin "6") (pinfunction "N.C-2_6") (pintype "passive"))
    )
    (net (code "61") (name "GND") (class "Default")
      (node (ref "C1") (pin "1") (pintype "passive"))
      (node (ref "C2") (pin "2") (pintype "passive"))
      (node (ref "C3") (pin "2") (pintype "passive"))
      (node (ref "C4") (pin "2") (pintype "passive"))
      (node (ref "C5") (pin "2") (pintype "passive"))
      (node (ref "C6") (pin "1") (pintype "passive"))
      (node (ref "C7") (pin "2") (pintype "passive"))
      (node (ref "C8") (pin "2") (pintype "passive"))
      (node (ref "D1") (pin "1") (pinfunction "GND_1") (pintype "passive"))
      (node (ref "D2") (pin "1") (pinfunction "-_1") (pintype "passive"))
      (node (ref "ICSP") (pin "6") (pinfunction "GND_6") (pintype "power_in"))
      (node (ref "IOH") (pin "7") (pinfunction "GND_7") (pintype "power_in"))
      (node (ref "J1") (pin "9") (pinfunction "9_9") (pintype "passive"))
      (node (ref "J3") (pin "5") (pinfunction "GND_5") (pintype "power_in"))
      (node (ref "J4") (pin "6") (pinfunction "Vss_6") (pintype "passive"))
      (node (ref "JP1") (pin "4") (pintype "passive"))
      (node (ref "JP2") (pin "4") (pintype "passive"))
      (node (ref "LED4") (pin "1") (pinfunction "C_1") (pintype "passive"))
      (node (ref "LED6") (pin "1") (pinfunction "C_1") (pintype "passive"))
      (node (ref "LED7") (pin "1") (pinfunction "C_1") (pintype "passive"))
      (node (ref "LED8") (pin "1") (pinfunction "C_1") (pintype "passive"))
      (node (ref "P1") (pin "25") (pinfunction "GND_25") (pintype "output"))
      (node (ref "P1") (pin "8") (pinfunction "GND_8") (pintype "power_in"))
      (node (ref "POWER") (pin "2") (pinfunction "GND_2") (pintype "power_in"))
      (node (ref "POWER") (pin "3") (pinfunction "GND_3") (pintype "power_in"))
      (node (ref "R14") (pin "1") (pinfunction "1_1") (pintype "passive"))
      (node (ref "R16") (pin "2") (pinfunction "2_2") (pintype "passive"))
      (node (ref "R23") (pin "2") (pinfunction "2_2") (pintype "passive"))
      (node (ref "R24") (pin "2") (pinfunction "2_2") (pintype "passive"))
      (node (ref "SW1") (pin "1") (pinfunction "N.O_1") (pintype "passive"))
      (node (ref "SW2") (pin "1") (pinfunction "N.O_1") (pintype "passive"))
      (node (ref "U1") (pin "3") (pinfunction "GND_3") (pintype "passive"))
    )
    (net (code "62") (name "ISO_GND") (class "Default")
      (node (ref "J2") (pin "4") (pinfunction "4_4") (pintype "passive"))
      (node (ref "LED2") (pin "1") (pinfunction "C_1") (pintype "passive"))
      (node (ref "LED3") (pin "1") (pinfunction "C_1") (pintype "passive"))
      (node (ref "LED9") (pin "1") (pinfunction "C_1") (pintype "passive"))
      (node (ref "P1") (pin "4") (pinfunction "GND_ISO_4") (pintype "power_in"))
    )
    (net (code "63") (name "Net-(D1-IO1)") (class "Default")
      (node (ref "D1") (pin "2") (pinfunction "IO1_2") (pintype "passive"))
      (node (ref "J3") (pin "2") (pinfunction "D-_2") (pintype "passive"))
      (node (ref "R13") (pin "2") (pinfunction "2_2") (pintype "passive"))
    )
    (net (code "64") (name "Net-(D1-IO2)") (class "Default")
      (node (ref "D1") (pin "3") (pinfunction "IO2_3") (pintype "passive"))
      (node (ref "J3") (pin "3") (pinfunction "D+_3") (pintype "passive"))
      (node (ref "R12") (pin "2") (pinfunction "2_2") (pintype "passive"))
    )
    (net (code "65") (name "Net-(D2-+)") (class "Default")
      (node (ref "D2") (pin "2") (pinfunction "+_2") (pintype "passive"))
      (node (ref "R3") (pin "1") (pinfunction "1_1") (pintype "passive"))
    )
    (net (code "66") (name "Net-(J3-Shield)") (class "Default")
      (node (ref "C1") (pin "2") (pintype "passive"))
      (node (ref "J3") (pin "6") (pinfunction "Shield_6") (pintype "power_in"))
      (node (ref "R14") (pin "2") (pinfunction "2_2") (pintype "passive"))
    )
    (net (code "67") (name "Net-(LED2-A)") (class "Default")
      (node (ref "LED2") (pin "2") (pinfunction "A_2") (pintype "passive"))
      (node (ref "R4") (pin "1") (pinfunction "1_1") (pintype "passive"))
    )
    (net (code "68") (name "Net-(LED3-A)") (class "Default")
      (node (ref "LED3") (pin "2") (pinfunction "A_2") (pintype "passive"))
      (node (ref "R5") (pin "1") (pinfunction "1_1") (pintype "passive"))
    )
    (net (code "69") (name "Net-(LED4-A)") (class "Default")
      (node (ref "LED4") (pin "2") (pinfunction "A_2") (pintype "passive"))
      (node (ref "R6") (pin "1") (pinfunction "1_1") (pintype "passive"))
    )
    (net (code "70") (name "Net-(LED5-A)") (class "Default")
      (node (ref "LED5") (pin "2") (pinfunction "A_2") (pintype "passive"))
      (node (ref "R8") (pin "2") (pinfunction "2_2") (pintype "passive"))
    )
    (net (code "71") (name "Net-(LED6-A)") (class "Default")
      (node (ref "LED6") (pin "2") (pinfunction "A_2") (pintype "passive"))
      (node (ref "R7") (pin "1") (pinfunction "1_1") (pintype "passive"))
    )
    (net (code "72") (name "Net-(LED7-A)") (class "Default")
      (node (ref "LED7") (pin "2") (pinfunction "A_2") (pintype "passive"))
      (node (ref "R9") (pin "1") (pinfunction "1_1") (pintype "passive"))
    )
    (net (code "73") (name "Net-(LED8-A)") (class "Default")
      (node (ref "LED8") (pin "2") (pinfunction "A_2") (pintype "passive"))
      (node (ref "R10") (pin "1") (pinfunction "1_1") (pintype "passive"))
    )
    (net (code "74") (name "Net-(LED9-A)") (class "Default")
      (node (ref "LED9") (pin "2") (pinfunction "A_2") (pintype "passive"))
      (node (ref "R11") (pin "1") (pinfunction "1_1") (pintype "passive"))
    )
    (net (code "75") (name "Net-(P1-HVI1)") (class "Default")
      (node (ref "J5") (pin "1") (pinfunction "1_1") (pintype "passive"))
      (node (ref "P1") (pin "33") (pinfunction "HVI1_33") (pintype "input"))
    )
    (net (code "76") (name "Net-(P1-HVI2)") (class "Default")
      (node (ref "J5") (pin "2") (pinfunction "2_2") (pintype "passive"))
      (node (ref "P1") (pin "34") (pinfunction "HVI2_34") (pintype "input"))
    )
    (net (code "77") (name "Net-(P1-HVI3)") (class "Default")
      (node (ref "J5") (pin "3") (pinfunction "3_3") (pintype "passive"))
      (node (ref "P1") (pin "35") (pinfunction "HVI3_35") (pintype "input"))
    )
    (net (code "78") (name "Net-(P1-N)") (class "Default")
      (node (ref "J5") (pin "4") (pinfunction "4_4") (pintype "passive"))
      (node (ref "P1") (pin "36") (pinfunction "N_36") (pintype "input"))
    )
    (net (code "79") (name "USB_3V3") (class "Default")
      (node (ref "C6") (pin "2") (pintype "passive"))
      (node (ref "C7") (pin "1") (pintype "passive"))
      (node (ref "R3") (pin "2") (pinfunction "2_2") (pintype "passive"))
      (node (ref "SW3") (pin "1") (pinfunction "N.O-1_1") (pintype "passive"))
      (node (ref "SW3") (pin "4") (pinfunction "N.O-2_4") (pintype "passive"))
      (node (ref "U1") (pin "2") (pinfunction "Vout_2") (pintype "passive"))
    )
    (net (code "80") (name "VBUS") (class "Default")
      (node (ref "C2") (pin "1") (pintype "passive"))
      (node (ref "C3") (pin "1") (pintype "passive"))
      (node (ref "C8") (pin "1") (pintype "passive"))
      (node (ref "D1") (pin "4") (pinfunction "VCC_4") (pintype "passive"))
      (node (ref "J3") (pin "1") (pinfunction "VBUS_1") (pintype "power_in"))
      (node (ref "POWER") (pin "1") (pinfunction "VIN_1") (pintype "power_in"))
      (node (ref "U1") (pin "1") (pinfunction "Vin_1") (pintype "passive"))
    )
    (net (code "81") (name "unconnected-(J1-Pad5)") (class "Default")
      (node (ref "J1") (pin "5") (pinfunction "5_5") (pintype "passive"))
    )
    (net (code "82") (name "unconnected-(J1-Pad10)") (class "Default")
      (node (ref "J1") (pin "10") (pinfunction "10_10") (pintype "passive"))
    )
    (net (code "83") (name "unconnected-(J3-ID-Pad4)") (class "Default")
      (node (ref "J3") (pin "4") (pinfunction "ID_4") (pintype "passive"))
    )
    (net (code "84") (name "unconnected-(J4-CMD-Pad3)") (class "Default")
      (node (ref "J4") (pin "3") (pinfunction "CMD_3") (pintype "passive+no_connect"))
    )
    (net (code "85") (name "unconnected-(J4-DAT2-Pad1)") (class "Default")
      (node (ref "J4") (pin "1") (pinfunction "DAT2_1") (pintype "passive+no_connect"))
    )
    (net (code "86") (name "unconnected-(J4-Pad9)") (class "Default")
      (node (ref "J4") (pin "9") (pinfunction "9_9") (pintype "passive+no_connect"))
    )
    (net (code "87") (name "unconnected-(J4-Pad10)") (class "Default")
      (node (ref "J4") (pin "10") (pinfunction "10_10") (pintype "passive+no_connect"))
    )
    (net (code "88") (name "unconnected-(POWER-Pad8)") (class "Default")
      (node (ref "POWER") (pin "8") (pintype "passive"))
    )
    (net (code "89") (name "unconnected-(POWER-RESET-Pad6)") (class "Default")
      (node (ref "POWER") (pin "6") (pinfunction "RESET_6") (pintype "passive"))
    )
  )
)
